# V1_0_1.net
KiCad netlist of a schematic drawn in EAGLE
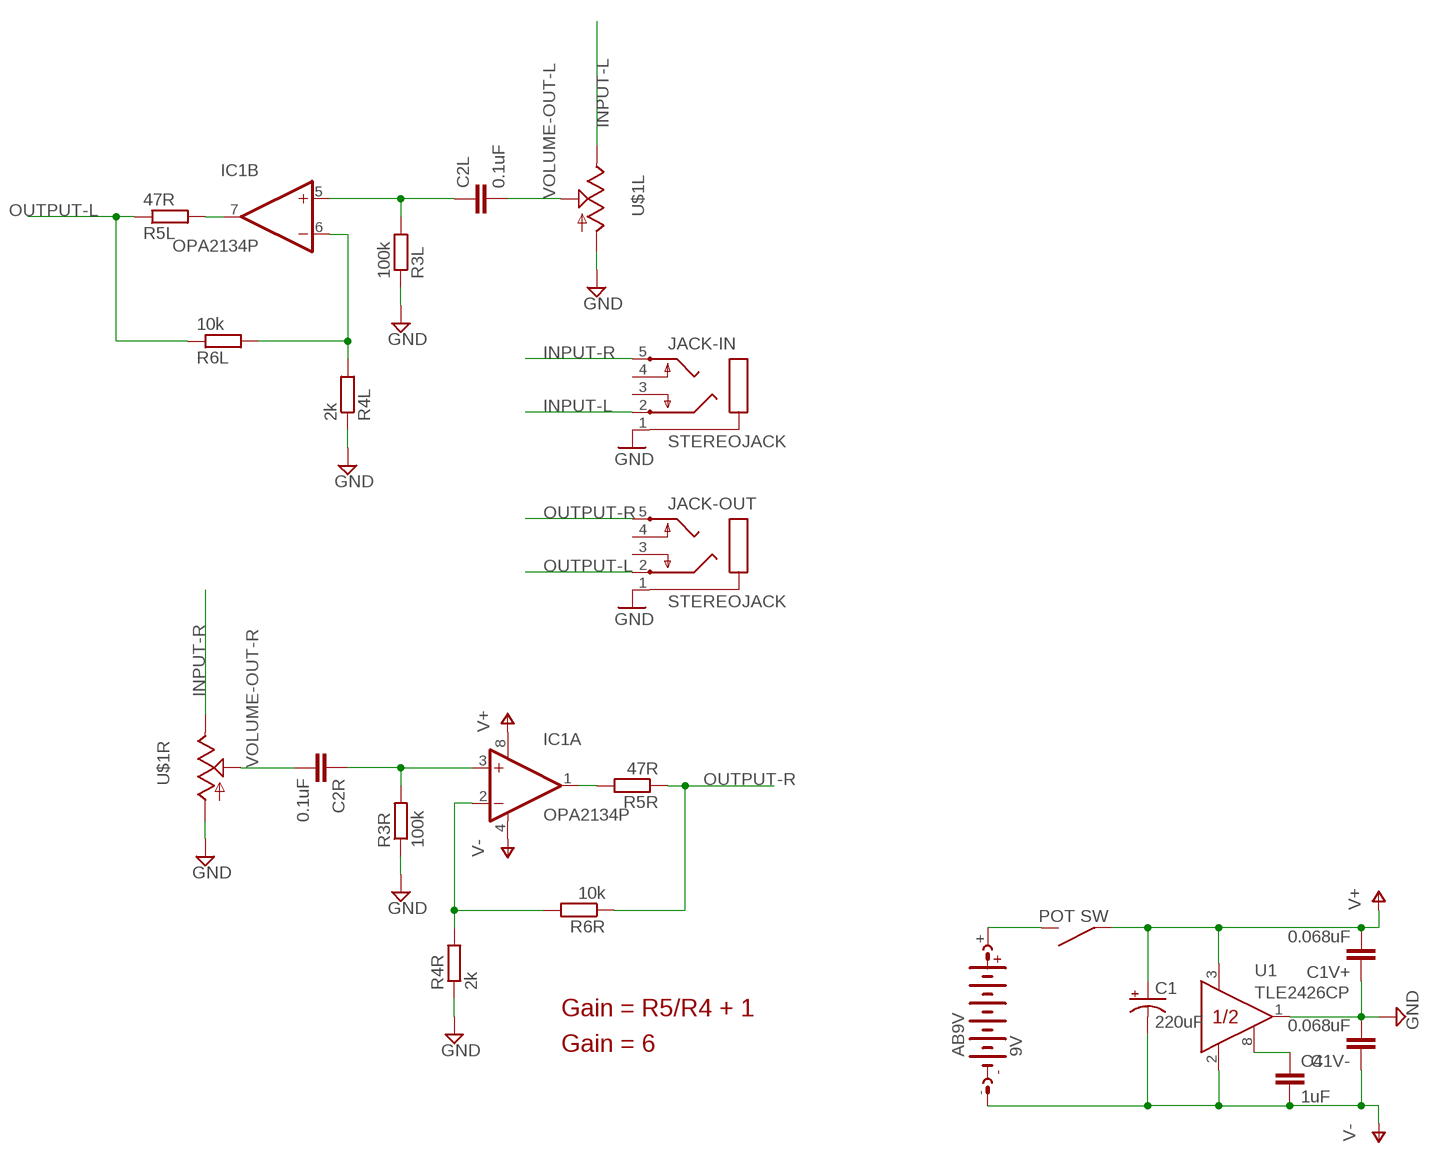
[diagram p0: schematic, sheet 1]

(export (version "E")
  (design (tool "Eeschema 10.0.6"))
  (components
    (comp (ref "9V")
      (value "AB9V")
      (footprint "eagle-import:AB9V")
      (libsource (lib "eagle-import") (part "AB9V"))
    )
    (comp (ref "C1")
      (value "220uF")
      (footprint "eagle-import:E3,5-8")
      (libsource (lib "eagle-import") (part "CPOL-USE3.5-8"))
    )
    (comp (ref "C1V+")
      (value "0.068uF")
      (footprint "eagle-import:C2.5-2")
      (libsource (lib "eagle-import") (part "C2.5/2"))
    )
    (comp (ref "C1V-")
      (value "0.068uF")
      (footprint "eagle-import:C2.5-2")
      (libsource (lib "eagle-import") (part "C2.5/2"))
    )
    (comp (ref "C2L")
      (value "0.1uF")
      (footprint "eagle-import:C5B5")
      (libsource (lib "eagle-import") (part "C5/5"))
    )
    (comp (ref "C2R")
      (value "0.1uF")
      (footprint "eagle-import:C5B5")
      (libsource (lib "eagle-import") (part "C5/5"))
    )
    (comp (ref "C4")
      (value "1uF")
      (footprint "eagle-import:C5B2.5")
      (libsource (lib "eagle-import") (part "C5/2.5"))
    )
    (comp (ref "IC1")
      (value "OPA2134P")
      (footprint "eagle-import:DIL-8")
      (libsource (lib "eagle-import") (part "OPA2134P"))
    )
    (comp (ref "JACK-IN")
      (value "STEREOJACK")
      (footprint "eagle-import:STX3100")
      (libsource (lib "eagle-import") (part "STEREOJACK"))
    )
    (comp (ref "JACK-OUT")
      (value "STEREOJACK")
      (footprint "eagle-import:STX3100")
      (libsource (lib "eagle-import") (part "STEREOJACK"))
    )
    (comp (ref "R3L")
      (value "100k")
      (footprint "eagle-import:0207_2V")
      (libsource (lib "eagle-import") (part "R-EU_0207/2V"))
    )
    (comp (ref "R3R")
      (value "100k")
      (footprint "eagle-import:0207_2V")
      (libsource (lib "eagle-import") (part "R-EU_0207/2V"))
    )
    (comp (ref "R4L")
      (value "2k")
      (footprint "eagle-import:0207_2V")
      (libsource (lib "eagle-import") (part "R-EU_0207/2V"))
    )
    (comp (ref "R4R")
      (value "2k")
      (footprint "eagle-import:0207_2V")
      (libsource (lib "eagle-import") (part "R-EU_0207/2V"))
    )
    (comp (ref "R5L")
      (value "47R")
      (footprint "eagle-import:0207_2V")
      (libsource (lib "eagle-import") (part "R-EU_0207/2V"))
    )
    (comp (ref "R5R")
      (value "47R")
      (footprint "eagle-import:0207_2V")
      (libsource (lib "eagle-import") (part "R-EU_0207/2V"))
    )
    (comp (ref "R6L")
      (value "10k")
      (footprint "eagle-import:0207_2V")
      (libsource (lib "eagle-import") (part "R-EU_0207/2V"))
    )
    (comp (ref "R6R")
      (value "10k")
      (footprint "eagle-import:0207_2V")
      (libsource (lib "eagle-import") (part "R-EU_0207/2V"))
    )
    (comp (ref "U$1")
      (value "ALPS_RK0971221Z05")
      (footprint "eagle-import:ALPS_RK0971221Z0X")
      (libsource (lib "eagle-import") (part "ALPS_RK0971221Z05"))
    )
    (comp (ref "U1")
      (value "TLE2426CP")
      (footprint "eagle-import:DIP-8")
      (libsource (lib "eagle-import") (part "TLE2426PC"))
    )
  )
  (nets
    (net (code "1") (name "/INPUT-L") (class "Default")
      (node (ref "JACK-IN") (pin "2") (pinfunction "2_2") (pintype "passive"))
      (node (ref "U$1") (pin "I1") (pinfunction "3_I1") (pintype "passive"))
    )
    (net (code "2") (name "/INPUT-R") (class "Default")
      (node (ref "JACK-IN") (pin "5") (pinfunction "5_5") (pintype "passive"))
      (node (ref "U$1") (pin "I2") (pinfunction "3_I2") (pintype "passive"))
    )
    (net (code "3") (name "/OUTPUT-L") (class "Default")
      (node (ref "JACK-OUT") (pin "2") (pinfunction "2_2") (pintype "passive"))
      (node (ref "R5L") (pin "1") (pinfunction "1_1") (pintype "passive"))
      (node (ref "R6L") (pin "1") (pinfunction "1_1") (pintype "passive"))
    )
    (net (code "4") (name "/OUTPUT-R") (class "Default")
      (node (ref "JACK-OUT") (pin "5") (pinfunction "5_5") (pintype "passive"))
      (node (ref "R5R") (pin "1") (pinfunction "1_1") (pintype "passive"))
      (node (ref "R6R") (pin "1") (pinfunction "1_1") (pintype "passive"))
    )
    (net (code "5") (name "/VOLUME-OUT-L") (class "Default")
      (node (ref "C2L") (pin "2") (pinfunction "2_2") (pintype "passive"))
      (node (ref "U$1") (pin "O1") (pinfunction "2_O1") (pintype "passive"))
    )
    (net (code "6") (name "/VOLUME-OUT-R") (class "Default")
      (node (ref "C2R") (pin "2") (pinfunction "2_2") (pintype "passive"))
      (node (ref "U$1") (pin "O2") (pinfunction "2_O2") (pintype "passive"))
    )
    (net (code "7") (name "GND") (class "Default")
      (node (ref "C1V+") (pin "1") (pinfunction "1_1") (pintype "passive"))
      (node (ref "C1V-") (pin "2") (pinfunction "2_2") (pintype "passive"))
      (node (ref "JACK-IN") (pin "1") (pinfunction "1_1") (pintype "passive"))
      (node (ref "JACK-OUT") (pin "1") (pinfunction "1_1") (pintype "passive"))
      (node (ref "R3L") (pin "1") (pinfunction "1_1") (pintype "passive"))
      (node (ref "R3R") (pin "1") (pinfunction "1_1") (pintype "passive"))
      (node (ref "R4L") (pin "1") (pinfunction "1_1") (pintype "passive"))
      (node (ref "R4R") (pin "1") (pinfunction "1_1") (pintype "passive"))
      (node (ref "U$1") (pin "G1") (pinfunction "1_G1") (pintype "passive"))
      (node (ref "U$1") (pin "G2") (pinfunction "1_G2") (pintype "passive"))
      (node (ref "U1") (pin "1") (pinfunction "OUT_1") (pintype "passive"))
    )
    (net (code "8") (name "Net-(9V-Pad+)") (class "Default")
      (node (ref "9V") (pin "+") (pinfunction "+_+") (pintype "passive"))
      (node (ref "U$1") (pin "S2") (pinfunction "S2_S2") (pintype "power_in"))
    )
    (net (code "9") (name "Net-(IC1A-+IN)") (class "Default")
      (node (ref "C2R") (pin "1") (pinfunction "1_1") (pintype "passive"))
      (node (ref "IC1") (pin "3") (pinfunction "+IN_3") (pintype "input"))
      (node (ref "R3R") (pin "2") (pinfunction "2_2") (pintype "passive"))
    )
    (net (code "10") (name "Net-(IC1A--IN)") (class "Default")
      (node (ref "IC1") (pin "2") (pinfunction "-IN_2") (pintype "input"))
      (node (ref "R4R") (pin "2") (pinfunction "2_2") (pintype "passive"))
      (node (ref "R6R") (pin "2") (pinfunction "2_2") (pintype "passive"))
    )
    (net (code "11") (name "Net-(IC1A-OUT)") (class "Default")
      (node (ref "IC1") (pin "1") (pinfunction "OUT_1") (pintype "output"))
      (node (ref "R5R") (pin "2") (pinfunction "2_2") (pintype "passive"))
    )
    (net (code "12") (name "Net-(IC1B-+IN)") (class "Default")
      (node (ref "C2L") (pin "1") (pinfunction "1_1") (pintype "passive"))
      (node (ref "IC1") (pin "5") (pinfunction "+IN_5") (pintype "input"))
      (node (ref "R3L") (pin "2") (pinfunction "2_2") (pintype "passive"))
    )
    (net (code "13") (name "Net-(IC1B--IN)") (class "Default")
      (node (ref "IC1") (pin "6") (pinfunction "-IN_6") (pintype "input"))
      (node (ref "R4L") (pin "2") (pinfunction "2_2") (pintype "passive"))
      (node (ref "R6L") (pin "2") (pinfunction "2_2") (pintype "passive"))
    )
    (net (code "14") (name "Net-(IC1B-OUT)") (class "Default")
      (node (ref "IC1") (pin "7") (pinfunction "OUT_7") (pintype "output"))
      (node (ref "R5L") (pin "2") (pinfunction "2_2") (pintype "passive"))
    )
    (net (code "15") (name "Net-(U1-NR)") (class "Default")
      (node (ref "C4") (pin "1") (pinfunction "1_1") (pintype "passive"))
      (node (ref "U1") (pin "8") (pinfunction "NR_8") (pintype "passive"))
    )
    (net (code "16") (name "V+") (class "Default")
      (node (ref "C1") (pin "+") (pinfunction "+_+") (pintype "passive"))
      (node (ref "C1V+") (pin "2") (pinfunction "2_2") (pintype "passive"))
      (node (ref "IC1") (pin "8") (pinfunction "V+_8") (pintype "power_in"))
      (node (ref "U$1") (pin "S1") (pinfunction "S1_S1") (pintype "power_in"))
      (node (ref "U1") (pin "3") (pinfunction "IN_3") (pintype "passive"))
    )
    (net (code "17") (name "V-") (class "Default")
      (node (ref "9V") (pin "-") (pinfunction "-_-") (pintype "passive"))
      (node (ref "C1") (pin "-") (pinfunction "-_-") (pintype "passive"))
      (node (ref "C1V-") (pin "1") (pinfunction "1_1") (pintype "passive"))
      (node (ref "C4") (pin "2") (pinfunction "2_2") (pintype "passive"))
      (node (ref "IC1") (pin "4") (pinfunction "V-_4") (pintype "power_in"))
      (node (ref "U1") (pin "2") (pinfunction "COM_2") (pintype "passive"))
    )
    (net (code "18") (name "unconnected-(JACK-IN-Pad3)") (class "Default")
      (node (ref "JACK-IN") (pin "3") (pinfunction "3_3") (pintype "passive"))
    )
    (net (code "19") (name "unconnected-(JACK-IN-Pad4)") (class "Default")
      (node (ref "JACK-IN") (pin "4") (pinfunction "4_4") (pintype "passive"))
    )
    (net (code "20") (name "unconnected-(JACK-OUT-Pad3)") (class "Default")
      (node (ref "JACK-OUT") (pin "3") (pinfunction "3_3") (pintype "passive"))
    )
    (net (code "21") (name "unconnected-(JACK-OUT-Pad4)") (class "Default")
      (node (ref "JACK-OUT") (pin "4") (pinfunction "4_4") (pintype "passive"))
    )
  )
)
